# PSPD_driver.net
KiCad netlist of a schematic drawn in EAGLE
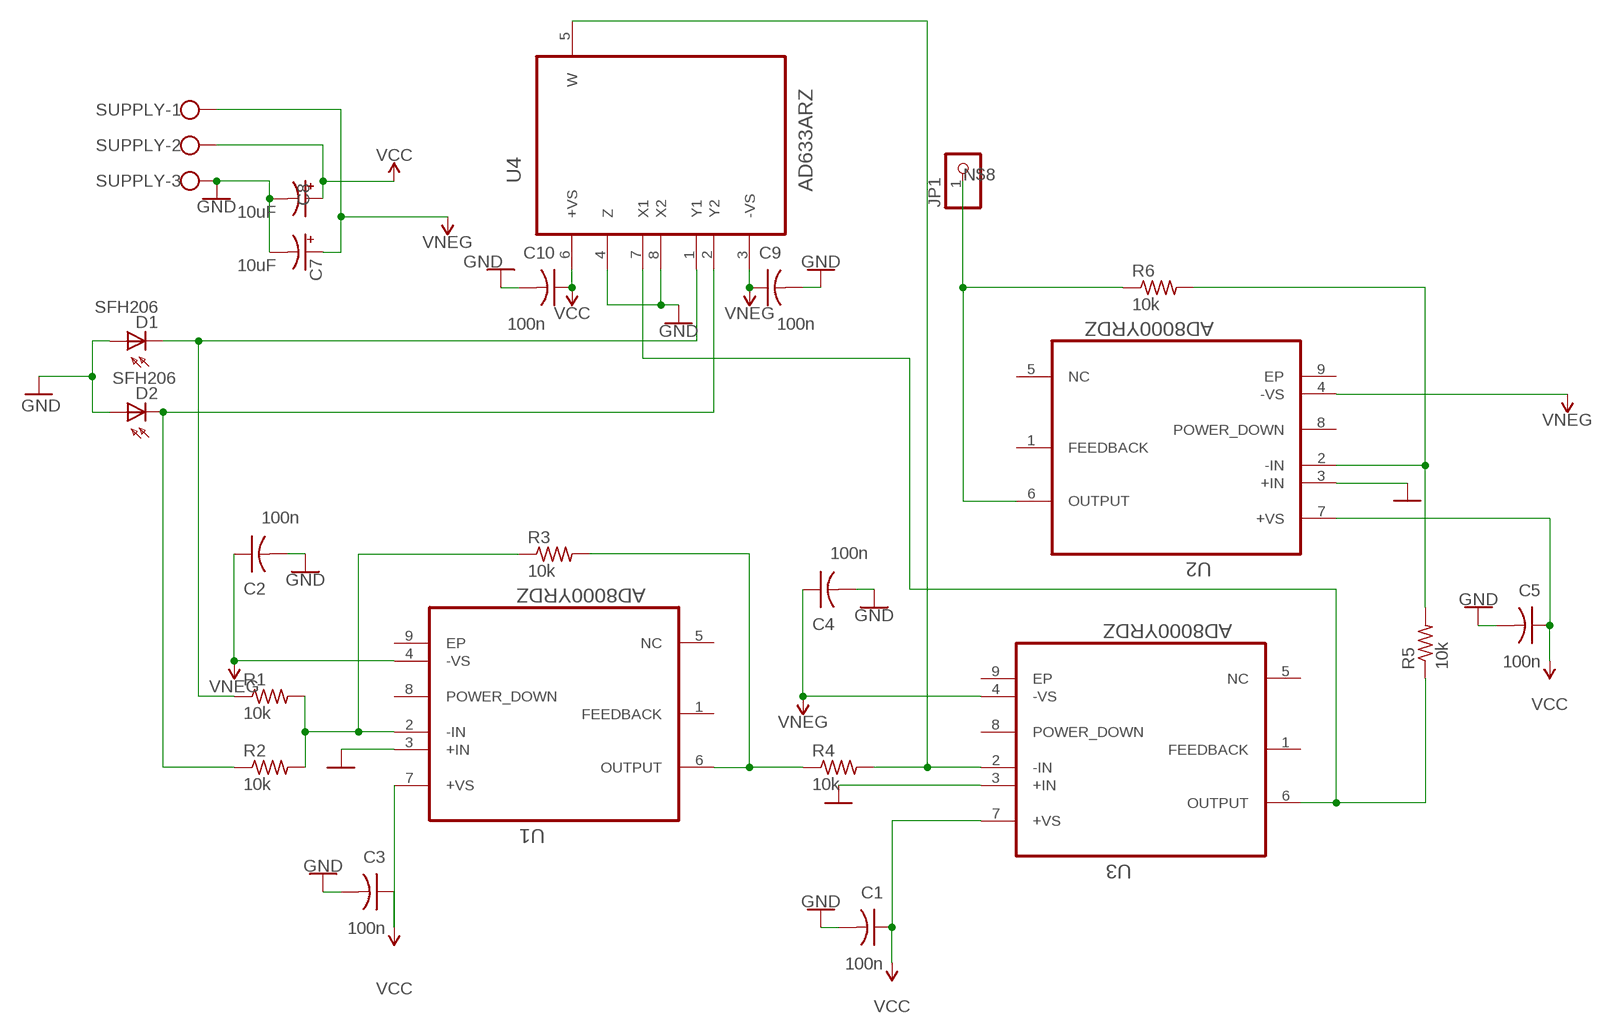
[diagram p0: schematic, sheet 1]

(export (version "E")
  (design (tool "Eeschema 10.0.6"))
  (components
    (comp (ref "C1")
      (value "100n")
      (footprint "eagle-import:C0805K")
      (libsource (lib "eagle-import") (part "C-USC0805K"))
    )
    (comp (ref "C2")
      (value "100n")
      (footprint "eagle-import:C0805K")
      (libsource (lib "eagle-import") (part "C-USC0805K"))
    )
    (comp (ref "C3")
      (value "100n")
      (footprint "eagle-import:C0805K")
      (libsource (lib "eagle-import") (part "C-USC0805K"))
    )
    (comp (ref "C4")
      (value "100n")
      (footprint "eagle-import:C0805K")
      (libsource (lib "eagle-import") (part "C-USC0805K"))
    )
    (comp (ref "C5")
      (value "100n")
      (footprint "eagle-import:C0805K")
      (libsource (lib "eagle-import") (part "C-USC0805K"))
    )
    (comp (ref "C7")
      (value "10uF")
      (footprint "eagle-import:CPOL-RADIAL-2.5MM-5MM")
      (libsource (lib "eagle-import") (part "10UF-POLAR-RADIAL-2.5MM-25V-20%"))
    )
    (comp (ref "C8")
      (value "10uF")
      (footprint "eagle-import:CPOL-RADIAL-2.5MM-5MM")
      (libsource (lib "eagle-import") (part "10UF-POLAR-RADIAL-2.5MM-25V-20%"))
    )
    (comp (ref "C9")
      (value "100n")
      (footprint "eagle-import:C0805K")
      (libsource (lib "eagle-import") (part "C-USC0805K"))
    )
    (comp (ref "C10")
      (value "100n")
      (footprint "eagle-import:C0805K")
      (libsource (lib "eagle-import") (part "C-USC0805K"))
    )
    (comp (ref "D1")
      (value "SFH206")
      (footprint "eagle-import:SFH206")
      (fields (field (name "MPN") "SFH206K"))
      (libsource (lib "eagle-import") (part "SFH206"))
    )
    (comp (ref "D2")
      (value "SFH206")
      (footprint "eagle-import:SFH206")
      (fields (field (name "MPN") "SFH206K"))
      (libsource (lib "eagle-import") (part "SFH206"))
    )
    (comp (ref "JP1")
      (value "PINHD-1X1")
      (footprint "eagle-import:1X01")
      (libsource (lib "eagle-import") (part "PINHD-1X1"))
    )
    (comp (ref "R1")
      (value "10k")
      (footprint "eagle-import:M0805")
      (libsource (lib "eagle-import") (part "R-US_M0805"))
    )
    (comp (ref "R2")
      (value "10k")
      (footprint "eagle-import:M0805")
      (libsource (lib "eagle-import") (part "R-US_M0805"))
    )
    (comp (ref "R3")
      (value "10k")
      (footprint "eagle-import:M0805")
      (libsource (lib "eagle-import") (part "R-US_M0805"))
    )
    (comp (ref "R4")
      (value "10k")
      (footprint "eagle-import:M0805")
      (libsource (lib "eagle-import") (part "R-US_M0805"))
    )
    (comp (ref "R5")
      (value "10k")
      (footprint "eagle-import:M0805")
      (libsource (lib "eagle-import") (part "R-US_M0805"))
    )
    (comp (ref "R6")
      (value "10k")
      (footprint "eagle-import:M0805")
      (libsource (lib "eagle-import") (part "R-US_M0805"))
    )
    (comp (ref "SUPPLY")
      (value "W237-103")
      (footprint "eagle-import:W237-103")
      (fields (field (name "MPN") "237-103"))
      (libsource (lib "eagle-import") (part "W237-103"))
    )
    (comp (ref "U1")
      (value "AD8000YRDZ")
      (footprint "eagle-import:SOIC127P600X175-9N")
      (fields (field (name "MF") "Analog Devices"))
      (libsource (lib "eagle-import") (part "AD8000YRDZ"))
    )
    (comp (ref "U2")
      (value "AD8000YRDZ")
      (footprint "eagle-import:SOIC127P600X175-9N")
      (fields (field (name "MF") "Analog Devices"))
      (libsource (lib "eagle-import") (part "AD8000YRDZ"))
    )
    (comp (ref "U3")
      (value "AD8000YRDZ")
      (footprint "eagle-import:SOIC127P600X175-9N")
      (fields (field (name "MF") "Analog Devices"))
      (libsource (lib "eagle-import") (part "AD8000YRDZ"))
    )
    (comp (ref "U4")
      (value "AD633ARZ")
      (footprint "eagle-import:SOIC127P600X175-8N")
      (fields (field (name "MF") "Analog Devices"))
      (libsource (lib "eagle-import") (part "AD633ARZ"))
    )
  )
  (nets
    (net (code "1") (name "/N$8") (class "Default")
      (node (ref "JP1") (pin "1") (pinfunction "1_1") (pintype "passive"))
      (node (ref "R6") (pin "1") (pinfunction "1_1") (pintype "passive"))
      (node (ref "U2") (pin "6") (pinfunction "OUTPUT_6") (pintype "output"))
    )
    (net (code "2") (name "GND") (class "Default")
      (node (ref "C1") (pin "2") (pinfunction "2_2") (pintype "passive"))
      (node (ref "C10") (pin "2") (pinfunction "2_2") (pintype "passive"))
      (node (ref "C2") (pin "2") (pinfunction "2_2") (pintype "passive"))
      (node (ref "C3") (pin "2") (pinfunction "2_2") (pintype "passive"))
      (node (ref "C4") (pin "2") (pinfunction "2_2") (pintype "passive"))
      (node (ref "C5") (pin "2") (pinfunction "2_2") (pintype "passive"))
      (node (ref "C7") (pin "2") (pinfunction "-_2") (pintype "passive"))
      (node (ref "C8") (pin "2") (pinfunction "-_2") (pintype "passive"))
      (node (ref "C9") (pin "2") (pinfunction "2_2") (pintype "passive"))
      (node (ref "D1") (pin "A") (pinfunction "A_A") (pintype "passive"))
      (node (ref "D2") (pin "A") (pinfunction "A_A") (pintype "passive"))
      (node (ref "SUPPLY") (pin "3") (pinfunction "KL_3") (pintype "passive"))
      (node (ref "U1") (pin "3") (pinfunction "+IN_3") (pintype "input"))
      (node (ref "U2") (pin "3") (pinfunction "+IN_3") (pintype "input"))
      (node (ref "U3") (pin "3") (pinfunction "+IN_3") (pintype "input"))
      (node (ref "U4") (pin "4") (pinfunction "Z_4") (pintype "input"))
      (node (ref "U4") (pin "8") (pinfunction "X2_8") (pintype "input"))
    )
    (net (code "3") (name "Net-(D1-C)") (class "Default")
      (node (ref "D1") (pin "K") (pinfunction "C_K") (pintype "passive"))
      (node (ref "R1") (pin "1") (pinfunction "1_1") (pintype "passive"))
      (node (ref "U4") (pin "1") (pinfunction "Y1_1") (pintype "input"))
    )
    (net (code "4") (name "Net-(D2-C)") (class "Default")
      (node (ref "D2") (pin "K") (pinfunction "C_K") (pintype "passive"))
      (node (ref "R2") (pin "1") (pinfunction "1_1") (pintype "passive"))
      (node (ref "U4") (pin "2") (pinfunction "Y2_2") (pintype "input"))
    )
    (net (code "5") (name "Net-(U1--IN)") (class "Default")
      (node (ref "R1") (pin "2") (pinfunction "2_2") (pintype "passive"))
      (node (ref "R2") (pin "2") (pinfunction "2_2") (pintype "passive"))
      (node (ref "R3") (pin "1") (pinfunction "1_1") (pintype "passive"))
      (node (ref "U1") (pin "2") (pinfunction "-IN_2") (pintype "input"))
    )
    (net (code "6") (name "Net-(U1-OUTPUT)") (class "Default")
      (node (ref "R3") (pin "2") (pinfunction "2_2") (pintype "passive"))
      (node (ref "R4") (pin "1") (pinfunction "1_1") (pintype "passive"))
      (node (ref "U1") (pin "6") (pinfunction "OUTPUT_6") (pintype "output"))
    )
    (net (code "7") (name "Net-(U2--IN)") (class "Default")
      (node (ref "R5") (pin "2") (pinfunction "2_2") (pintype "passive"))
      (node (ref "R6") (pin "2") (pinfunction "2_2") (pintype "passive"))
      (node (ref "U2") (pin "2") (pinfunction "-IN_2") (pintype "input"))
    )
    (net (code "8") (name "Net-(U3--IN)") (class "Default")
      (node (ref "R4") (pin "2") (pinfunction "2_2") (pintype "passive"))
      (node (ref "U3") (pin "2") (pinfunction "-IN_2") (pintype "input"))
      (node (ref "U4") (pin "5") (pinfunction "W_5") (pintype "output"))
    )
    (net (code "9") (name "Net-(U3-OUTPUT)") (class "Default")
      (node (ref "R5") (pin "1") (pinfunction "1_1") (pintype "passive"))
      (node (ref "U3") (pin "6") (pinfunction "OUTPUT_6") (pintype "output"))
      (node (ref "U4") (pin "7") (pinfunction "X1_7") (pintype "input"))
    )
    (net (code "10") (name "VCC") (class "Default")
      (node (ref "C1") (pin "1") (pinfunction "1_1") (pintype "passive"))
      (node (ref "C10") (pin "1") (pinfunction "1_1") (pintype "passive"))
      (node (ref "C3") (pin "1") (pinfunction "1_1") (pintype "passive"))
      (node (ref "C5") (pin "1") (pinfunction "1_1") (pintype "passive"))
      (node (ref "C8") (pin "1") (pinfunction "+_1") (pintype "passive"))
      (node (ref "SUPPLY") (pin "2") (pinfunction "KL_2") (pintype "passive"))
      (node (ref "U1") (pin "7") (pinfunction "+VS_7") (pintype "power_in"))
      (node (ref "U2") (pin "7") (pinfunction "+VS_7") (pintype "power_in"))
      (node (ref "U3") (pin "7") (pinfunction "+VS_7") (pintype "power_in"))
      (node (ref "U4") (pin "6") (pinfunction "+VS_6") (pintype "power_in"))
    )
    (net (code "11") (name "VNEG") (class "Default")
      (node (ref "C2") (pin "1") (pinfunction "1_1") (pintype "passive"))
      (node (ref "C4") (pin "1") (pinfunction "1_1") (pintype "passive"))
      (node (ref "C7") (pin "1") (pinfunction "+_1") (pintype "passive"))
      (node (ref "C9") (pin "1") (pinfunction "1_1") (pintype "passive"))
      (node (ref "SUPPLY") (pin "1") (pinfunction "KL_1") (pintype "passive"))
      (node (ref "U1") (pin "4") (pinfunction "-VS_4") (pintype "power_in"))
      (node (ref "U2") (pin "4") (pinfunction "-VS_4") (pintype "power_in"))
      (node (ref "U3") (pin "4") (pinfunction "-VS_4") (pintype "power_in"))
      (node (ref "U4") (pin "3") (pinfunction "-VS_3") (pintype "power_in"))
    )
    (net (code "12") (name "unconnected-(U1-EP-Pad9)") (class "Default")
      (node (ref "U1") (pin "9") (pinfunction "EP_9") (pintype "passive"))
    )
    (net (code "13") (name "unconnected-(U1-FEEDBACK-Pad1)") (class "Default")
      (node (ref "U1") (pin "1") (pinfunction "FEEDBACK_1") (pintype "input"))
    )
    (net (code "14") (name "unconnected-(U1-NC-Pad5)") (class "Default")
      (node (ref "U1") (pin "5") (pinfunction "NC_5") (pintype "no_connect"))
    )
    (net (code "15") (name "unconnected-(U1-POWER_DOWN-Pad8)") (class "Default")
      (node (ref "U1") (pin "8") (pinfunction "POWER_DOWN_8") (pintype "input"))
    )
    (net (code "16") (name "unconnected-(U2-EP-Pad9)") (class "Default")
      (node (ref "U2") (pin "9") (pinfunction "EP_9") (pintype "passive"))
    )
    (net (code "17") (name "unconnected-(U2-FEEDBACK-Pad1)") (class "Default")
      (node (ref "U2") (pin "1") (pinfunction "FEEDBACK_1") (pintype "input"))
    )
    (net (code "18") (name "unconnected-(U2-NC-Pad5)") (class "Default")
      (node (ref "U2") (pin "5") (pinfunction "NC_5") (pintype "no_connect"))
    )
    (net (code "19") (name "unconnected-(U2-POWER_DOWN-Pad8)") (class "Default")
      (node (ref "U2") (pin "8") (pinfunction "POWER_DOWN_8") (pintype "input"))
    )
    (net (code "20") (name "unconnected-(U3-EP-Pad9)") (class "Default")
      (node (ref "U3") (pin "9") (pinfunction "EP_9") (pintype "passive"))
    )
    (net (code "21") (name "unconnected-(U3-FEEDBACK-Pad1)") (class "Default")
      (node (ref "U3") (pin "1") (pinfunction "FEEDBACK_1") (pintype "input"))
    )
    (net (code "22") (name "unconnected-(U3-NC-Pad5)") (class "Default")
      (node (ref "U3") (pin "5") (pinfunction "NC_5") (pintype "no_connect"))
    )
    (net (code "23") (name "unconnected-(U3-POWER_DOWN-Pad8)") (class "Default")
      (node (ref "U3") (pin "8") (pinfunction "POWER_DOWN_8") (pintype "input"))
    )
  )
)
